# dynext_v0_1.net
KiCad netlist of a schematic drawn in EAGLE
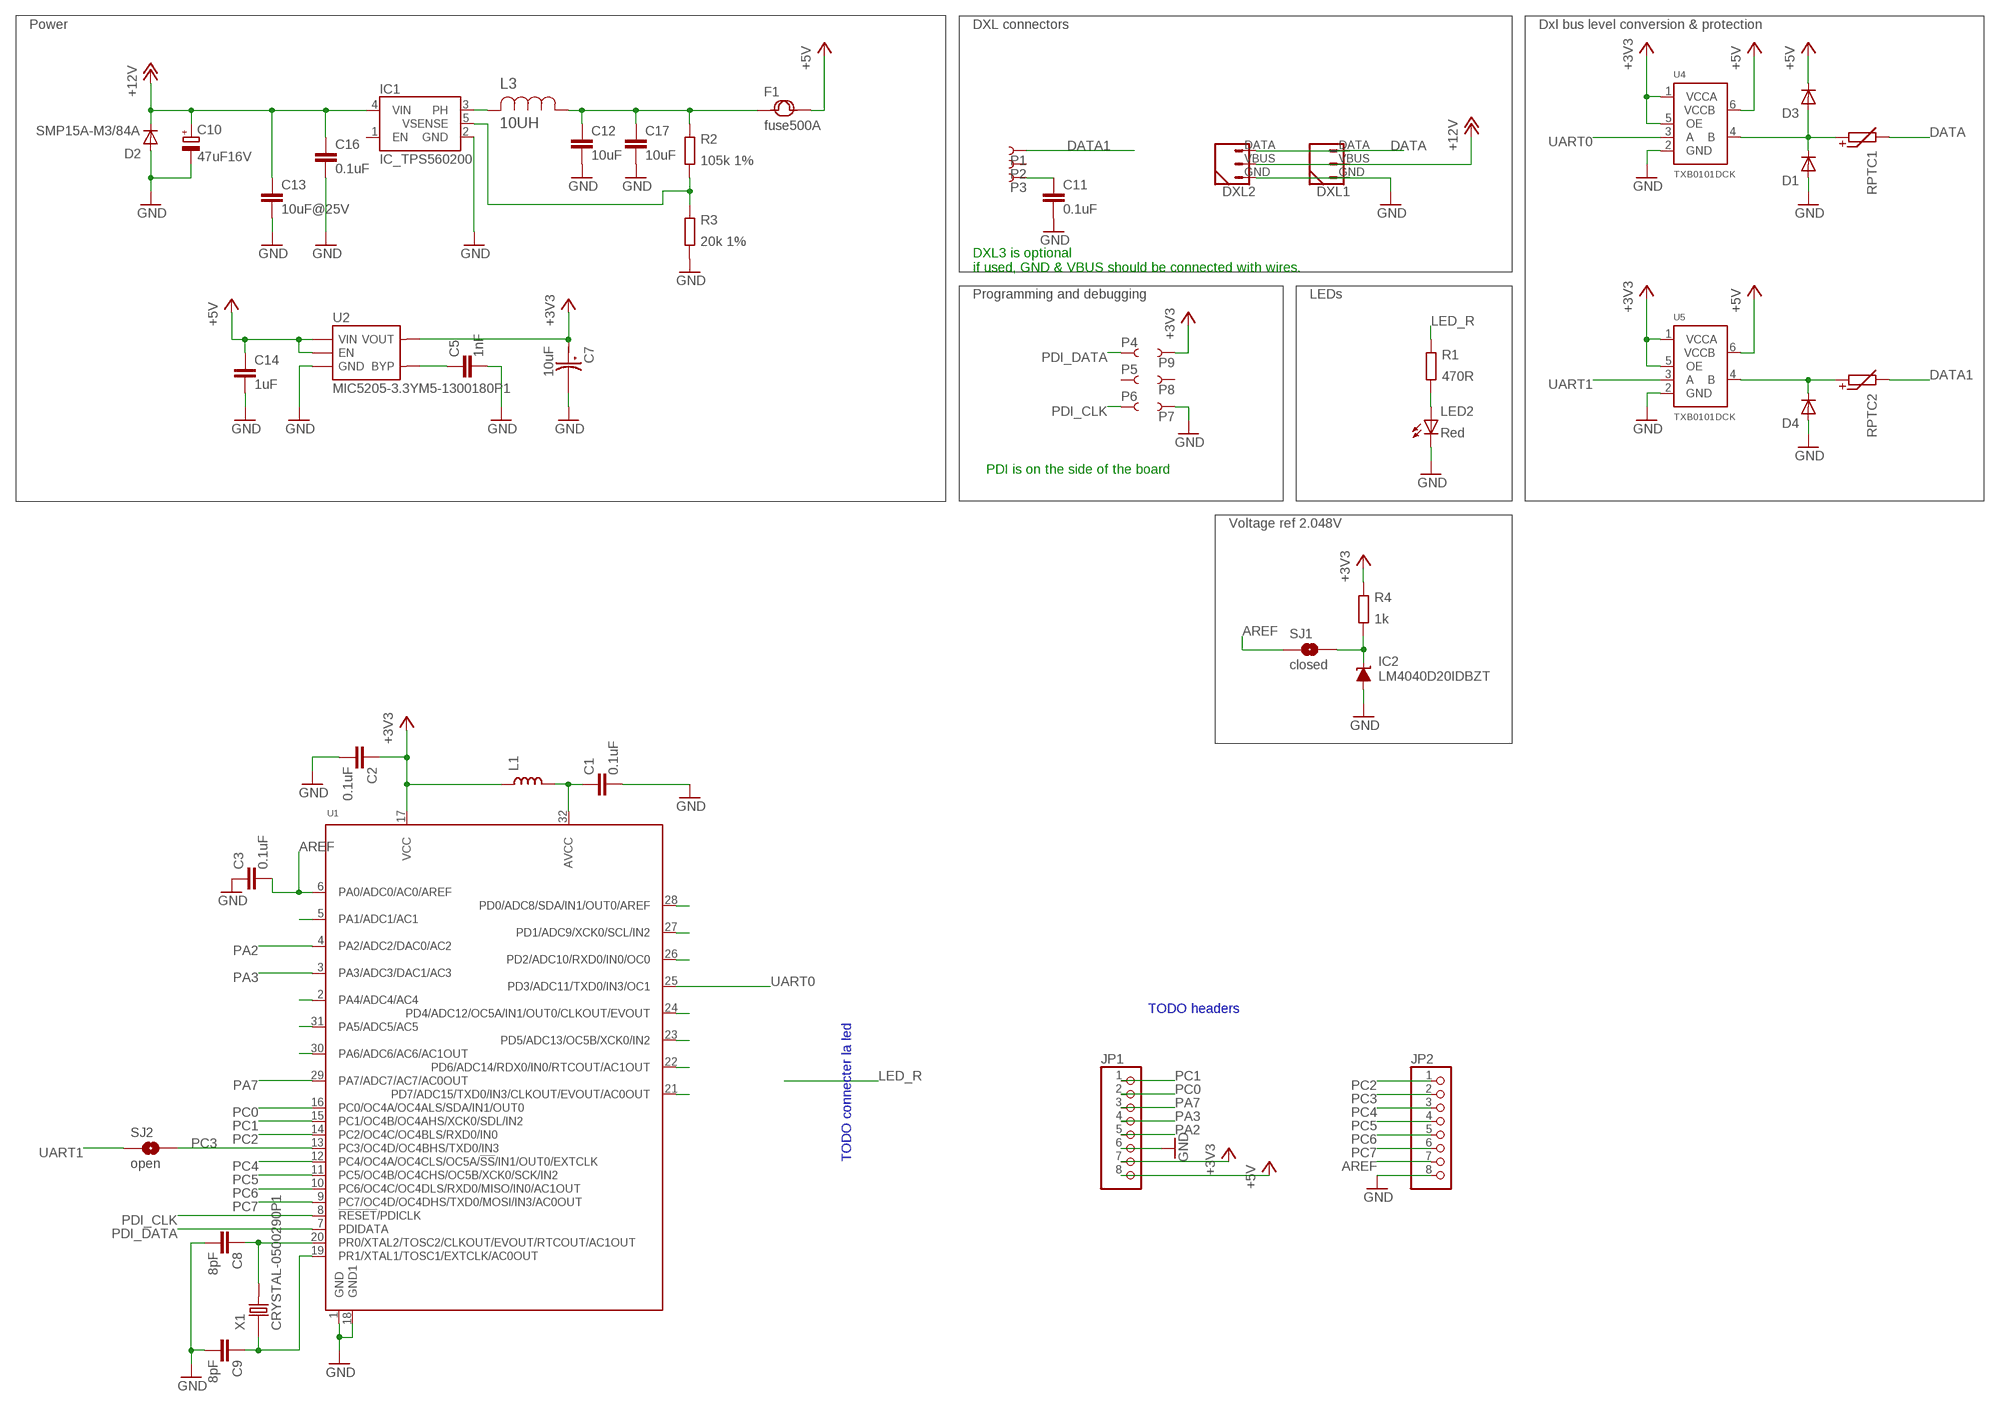
[diagram p0: schematic, sheet 1]

(export (version "E")
  (design (tool "Eeschema 10.0.6"))
  (components
    (comp (ref "C1")
      (value "0.1uF")
      (footprint "eagle-import:0402_N")
      (libsource (lib "eagle-import") (part "C0402"))
    )
    (comp (ref "C2")
      (value "0.1uF")
      (footprint "eagle-import:0402_N")
      (libsource (lib "eagle-import") (part "C0402"))
    )
    (comp (ref "C3")
      (value "0.1uF")
      (footprint "eagle-import:0402_N")
      (libsource (lib "eagle-import") (part "C0402"))
    )
    (comp (ref "C5")
      (value "1nF")
      (footprint "eagle-import:0402_N")
      (libsource (lib "eagle-import") (part "C0402"))
    )
    (comp (ref "C7")
      (value "10uF")
      (footprint "eagle-import:AVX-A")
      (libsource (lib "eagle-import") (part "C-POLAR-A"))
    )
    (comp (ref "C8")
      (value "8pF")
      (footprint "eagle-import:0402_N")
      (libsource (lib "eagle-import") (part "C0402"))
    )
    (comp (ref "C9")
      (value "8pF")
      (footprint "eagle-import:0402_N")
      (libsource (lib "eagle-import") (part "C0402"))
    )
    (comp (ref "C10")
      (value "47uF16V")
      (footprint "eagle-import:UD-5X5,8_NICHICON")
      (libsource (lib "eagle-import") (part "CPOL-EUUD-5X5,8"))
    )
    (comp (ref "C11")
      (value "0.1uF")
      (footprint "eagle-import:0402_N")
      (libsource (lib "eagle-import") (part "C0402"))
    )
    (comp (ref "C12")
      (value "10uF")
      (footprint "eagle-import:0805_N")
      (libsource (lib "eagle-import") (part "C0805"))
    )
    (comp (ref "C13")
      (value "10uF@25V")
      (footprint "eagle-import:0805_N")
      (libsource (lib "eagle-import") (part "C0805"))
    )
    (comp (ref "C14")
      (value "1uF")
      (footprint "eagle-import:0402_N")
      (libsource (lib "eagle-import") (part "C0402"))
    )
    (comp (ref "C16")
      (value "0.1uF")
      (footprint "eagle-import:0402_N")
      (libsource (lib "eagle-import") (part "C0402"))
    )
    (comp (ref "C17")
      (value "10uF")
      (footprint "eagle-import:0805_N")
      (libsource (lib "eagle-import") (part "C0805"))
    )
    (comp (ref "D1")
      (value "DIODE-SOD523")
      (footprint "eagle-import:SOD-523_N")
      (libsource (lib "eagle-import") (part "DIODE-SOD523"))
    )
    (comp (ref "D2")
      (value "SMP15A-M3/84A")
      (footprint "eagle-import:DO-220AA")
      (libsource (lib "eagle-import") (part "DIODE-SMP"))
    )
    (comp (ref "D3")
      (value "DIODE-SOD523")
      (footprint "eagle-import:SOD-523_N")
      (libsource (lib "eagle-import") (part "DIODE-SOD523"))
    )
    (comp (ref "D4")
      (value "DIODE-SOD523")
      (footprint "eagle-import:SOD-523_N")
      (libsource (lib "eagle-import") (part "DIODE-SOD523"))
    )
    (comp (ref "DXL1")
      (value "DYNAMIXEL_3POS-T")
      (footprint "eagle-import:DYNAMIXEL_3POS_TOP")
      (libsource (lib "eagle-import") (part "DYNAMIXEL_3POS-T"))
    )
    (comp (ref "DXL2")
      (value "DYNAMIXEL_3POS-T")
      (footprint "eagle-import:DYNAMIXEL_3POS_TOP")
      (libsource (lib "eagle-import") (part "DYNAMIXEL_3POS-T"))
    )
    (comp (ref "F1")
      (value "fuse500A")
      (footprint "eagle-import:F1206")
      (libsource (lib "eagle-import") (part "FUSE-1206"))
    )
    (comp (ref "IC1")
      (value "IC_TPS560200")
      (footprint "eagle-import:SOT-23-5_N")
      (libsource (lib "eagle-import") (part "IC_TPS560200"))
    )
    (comp (ref "IC2")
      (value "LM4040D20IDBZT")
      (footprint "eagle-import:DBZ_R-PDSO-G3")
      (fields (field (name "MPN") "LM4041A12IDBZR"))
      (libsource (lib "eagle-import") (part "LM4041DBZA12"))
    )
    (comp (ref "JP1")
      (value "PINHD-1X8R")
      (footprint "eagle-import:1X08_ROUND")
      (libsource (lib "eagle-import") (part "PINHD-1X8R"))
    )
    (comp (ref "JP2")
      (value "PINHD-1X8R")
      (footprint "eagle-import:1X08_ROUND")
      (libsource (lib "eagle-import") (part "PINHD-1X8R"))
    )
    (comp (ref "L1")
      (value "L0603")
      (footprint "eagle-import:0603_N")
      (libsource (lib "eagle-import") (part "L0603"))
    )
    (comp (ref "L3")
      (value "10UH")
      (footprint "eagle-import:IND_ELL4XG")
      (fields (field (name "MPN") "ELL4LG100MA"))
      (libsource (lib "eagle-import") (part "ELL-4XG4LG100MA"))
    )
    (comp (ref "LED2")
      (value "Red")
      (footprint "eagle-import:D_0603_N")
      (libsource (lib "eagle-import") (part "LED0603"))
    )
    (comp (ref "P1")
      (value "PIN_SMD_2X2.5")
      (footprint "eagle-import:PIN_SMD_2X2.5")
      (libsource (lib "eagle-import") (part "PIN_SMD_2X2.5"))
    )
    (comp (ref "P2")
      (value "PIN_SMD_2X2.5")
      (footprint "eagle-import:PIN_SMD_2X2.5")
      (libsource (lib "eagle-import") (part "PIN_SMD_2X2.5"))
    )
    (comp (ref "P3")
      (value "PIN_SMD_2X2.5")
      (footprint "eagle-import:PIN_SMD_2X2.5")
      (libsource (lib "eagle-import") (part "PIN_SMD_2X2.5"))
    )
    (comp (ref "P4")
      (value "PIN_SMD_2X2.5")
      (footprint "eagle-import:PIN_SMD_2X2.5")
      (libsource (lib "eagle-import") (part "PIN_SMD_2X2.5"))
    )
    (comp (ref "P5")
      (value "PIN_SMD_1X1")
      (footprint "eagle-import:PIN_SMD_1X1")
      (libsource (lib "eagle-import") (part "PIN_SMD_1X1"))
    )
    (comp (ref "P6")
      (value "PIN_SMD_2X2.5")
      (footprint "eagle-import:PIN_SMD_2X2.5")
      (libsource (lib "eagle-import") (part "PIN_SMD_2X2.5"))
    )
    (comp (ref "P7")
      (value "PIN_SMD_2X2.5")
      (footprint "eagle-import:PIN_SMD_2X2.5")
      (libsource (lib "eagle-import") (part "PIN_SMD_2X2.5"))
    )
    (comp (ref "P8")
      (value "PIN_SMD_1X1")
      (footprint "eagle-import:PIN_SMD_1X1")
      (libsource (lib "eagle-import") (part "PIN_SMD_1X1"))
    )
    (comp (ref "P9")
      (value "PIN_SMD_2X2.5")
      (footprint "eagle-import:PIN_SMD_2X2.5")
      (libsource (lib "eagle-import") (part "PIN_SMD_2X2.5"))
    )
    (comp (ref "R1")
      (value "470R")
      (footprint "eagle-import:0402_N")
      (libsource (lib "eagle-import") (part "R0402"))
    )
    (comp (ref "R2")
      (value "105k 1%")
      (footprint "eagle-import:0402_N")
      (libsource (lib "eagle-import") (part "R0402"))
    )
    (comp (ref "R3")
      (value "20k 1%")
      (footprint "eagle-import:0402_N")
      (libsource (lib "eagle-import") (part "R0402"))
    )
    (comp (ref "R4")
      (value "1k")
      (footprint "eagle-import:0402_N")
      (libsource (lib "eagle-import") (part "R0402"))
    )
    (comp (ref "RPTC1")
      (value "R-PTC0603")
      (footprint "eagle-import:0603_N")
      (libsource (lib "eagle-import") (part "R-PTC0603"))
    )
    (comp (ref "RPTC2")
      (value "R-PTC0603")
      (footprint "eagle-import:0603_N")
      (libsource (lib "eagle-import") (part "R-PTC0603"))
    )
    (comp (ref "SJ1")
      (value "closed")
      (footprint "eagle-import:SJ_2S-TRACE2")
      (libsource (lib "eagle-import") (part "SOLDERJUMPER2_TRACE2"))
    )
    (comp (ref "SJ2")
      (value "open")
      (footprint "eagle-import:SJ_2S-NO")
      (libsource (lib "eagle-import") (part "SOLDERJUMPER2NO"))
    )
    (comp (ref "U1")
      (value "ATXMEGAE5-MU_MOD")
      (footprint "eagle-import:QFN-32_50P_L_MOD")
      (libsource (lib "eagle-import") (part "ATXMEGAE5-MU_MOD"))
    )
    (comp (ref "U2")
      (value "MIC5205-3.3YM5-1300180P1")
      (footprint "eagle-import:SOT23-5")
      (libsource (lib "eagle-import") (part "MIC5205-3.3YM5-1300180P1"))
    )
    (comp (ref "U4")
      (value "TXB0101DCK")
      (footprint "eagle-import:SC70-6")
      (libsource (lib "eagle-import") (part "TXB0101DCK"))
    )
    (comp (ref "U5")
      (value "TXB0101DCK")
      (footprint "eagle-import:SC70-6")
      (libsource (lib "eagle-import") (part "TXB0101DCK"))
    )
    (comp (ref "X1")
      (value "CRYSTAL-0500290P1")
      (footprint "eagle-import:2P-SMD-5.0X3.2")
      (libsource (lib "eagle-import") (part "CRYSTAL-0500290P1"))
    )
  )
  (nets
    (net (code "1") (name "+3V3") (class "Default")
      (node (ref "C2") (pin "1") (pinfunction "1_1") (pintype "passive"))
      (node (ref "C7") (pin "+") (pinfunction "1_+") (pintype "bidirectional"))
      (node (ref "JP1") (pin "7") (pinfunction "7_7") (pintype "passive"))
      (node (ref "L1") (pin "1") (pinfunction "1_1") (pintype "passive"))
      (node (ref "P9") (pin "PIN") (pinfunction "1_PIN") (pintype "bidirectional"))
      (node (ref "R4") (pin "2") (pinfunction "2_2") (pintype "passive"))
      (node (ref "U1") (pin "17") (pinfunction "VCC_17") (pintype "bidirectional"))
      (node (ref "U2") (pin "5") (pinfunction "VOUT_5") (pintype "bidirectional"))
      (node (ref "U4") (pin "1") (pinfunction "VCCA_1") (pintype "bidirectional"))
      (node (ref "U4") (pin "5") (pinfunction "OE_5") (pintype "bidirectional"))
      (node (ref "U5") (pin "1") (pinfunction "VCCA_1") (pintype "bidirectional"))
      (node (ref "U5") (pin "5") (pinfunction "OE_5") (pintype "bidirectional"))
    )
    (net (code "2") (name "+5V") (class "Default")
      (node (ref "C14") (pin "1") (pinfunction "1_1") (pintype "passive"))
      (node (ref "D3") (pin "C") (pinfunction "C_C") (pintype "passive"))
      (node (ref "F1") (pin "2") (pinfunction "2_2") (pintype "bidirectional"))
      (node (ref "JP1") (pin "8") (pinfunction "8_8") (pintype "passive"))
      (node (ref "U2") (pin "1") (pinfunction "VIN_1") (pintype "bidirectional"))
      (node (ref "U2") (pin "3") (pinfunction "EN_3") (pintype "bidirectional"))
      (node (ref "U4") (pin "6") (pinfunction "VCCB_6") (pintype "bidirectional"))
      (node (ref "U5") (pin "6") (pinfunction "VCCB_6") (pintype "bidirectional"))
    )
    (net (code "3") (name "+12V") (class "Default")
      (node (ref "C10") (pin "+") (pinfunction "+_+") (pintype "passive"))
      (node (ref "C13") (pin "1") (pinfunction "1_1") (pintype "passive"))
      (node (ref "C16") (pin "1") (pinfunction "1_1") (pintype "passive"))
      (node (ref "D2") (pin "C") (pinfunction "C_C") (pintype "passive"))
      (node (ref "DXL1") (pin "VBUS") (pinfunction "2_VBUS") (pintype "bidirectional"))
      (node (ref "DXL2") (pin "VBUS") (pinfunction "2_VBUS") (pintype "bidirectional"))
      (node (ref "IC1") (pin "4") (pinfunction "VIN_4") (pintype "bidirectional"))
    )
    (net (code "4") (name "/AREF") (class "Default")
      (node (ref "C3") (pin "2") (pinfunction "2_2") (pintype "passive"))
      (node (ref "JP2") (pin "7") (pinfunction "7_7") (pintype "passive"))
      (node (ref "SJ1") (pin "1") (pinfunction "1_1") (pintype "passive"))
      (node (ref "U1") (pin "6") (pinfunction "PA0/ADC0/AC0/AREF_6") (pintype "bidirectional"))
    )
    (net (code "5") (name "/DATA") (class "Default")
      (node (ref "DXL1") (pin "DATA") (pinfunction "3_DATA") (pintype "bidirectional"))
      (node (ref "DXL2") (pin "DATA") (pinfunction "3_DATA") (pintype "bidirectional"))
      (node (ref "RPTC1") (pin "2") (pinfunction "2_2") (pintype "passive"))
    )
    (net (code "6") (name "/DATA1") (class "Default")
      (node (ref "P1") (pin "PIN") (pinfunction "1_PIN") (pintype "bidirectional"))
      (node (ref "RPTC2") (pin "2") (pinfunction "2_2") (pintype "passive"))
    )
    (net (code "7") (name "/LED_R") (class "Default")
      (node (ref "R1") (pin "2") (pinfunction "2_2") (pintype "passive"))
    )
    (net (code "8") (name "/PA2") (class "Default")
      (node (ref "JP1") (pin "5") (pinfunction "5_5") (pintype "passive"))
      (node (ref "U1") (pin "4") (pinfunction "PA2/ADC2/DAC0/AC2_4") (pintype "bidirectional"))
    )
    (net (code "9") (name "/PA3") (class "Default")
      (node (ref "JP1") (pin "4") (pinfunction "4_4") (pintype "passive"))
      (node (ref "U1") (pin "3") (pinfunction "PA3/ADC3/DAC1/AC3_3") (pintype "bidirectional"))
    )
    (net (code "10") (name "/PA7") (class "Default")
      (node (ref "JP1") (pin "3") (pinfunction "3_3") (pintype "passive"))
      (node (ref "U1") (pin "29") (pinfunction "PA7/ADC7/AC7/AC0OUT_29") (pintype "bidirectional"))
    )
    (net (code "11") (name "/PC0") (class "Default")
      (node (ref "JP1") (pin "2") (pinfunction "2_2") (pintype "passive"))
      (node (ref "U1") (pin "16") (pinfunction "PC0/OC4A/OC4ALS/SDA/IN1/OUT0_16") (pintype "bidirectional"))
    )
    (net (code "12") (name "/PC1") (class "Default")
      (node (ref "JP1") (pin "1") (pinfunction "1_1") (pintype "passive"))
      (node (ref "U1") (pin "15") (pinfunction "PC1/OC4B/OC4AHS/XCK0/SDL/IN2_15") (pintype "bidirectional"))
    )
    (net (code "13") (name "/PC2") (class "Default")
      (node (ref "JP2") (pin "1") (pinfunction "1_1") (pintype "passive"))
      (node (ref "U1") (pin "14") (pinfunction "PC2/OC4C/OC4BLS/RXD0/IN0_14") (pintype "bidirectional"))
    )
    (net (code "14") (name "/PC3") (class "Default")
      (node (ref "JP2") (pin "2") (pinfunction "2_2") (pintype "passive"))
      (node (ref "SJ2") (pin "2") (pinfunction "2_2") (pintype "passive"))
      (node (ref "U1") (pin "13") (pinfunction "PC3/OC4D/OC4BHS/TXD0/IN3_13") (pintype "bidirectional"))
    )
    (net (code "15") (name "/PC4") (class "Default")
      (node (ref "JP2") (pin "3") (pinfunction "3_3") (pintype "passive"))
      (node (ref "U1") (pin "12") (pinfunction "PC4/OC4A/OC4CLS/OC5A/~{SS}/IN1/OUT0/EXTCLK_12") (pintype "bidirectional"))
    )
    (net (code "16") (name "/PC5") (class "Default")
      (node (ref "JP2") (pin "4") (pinfunction "4_4") (pintype "passive"))
      (node (ref "U1") (pin "11") (pinfunction "PC5/OC4B/OC4CHS/OC5B/XCK0/SCK/IN2_11") (pintype "bidirectional"))
    )
    (net (code "17") (name "/PC6") (class "Default")
      (node (ref "JP2") (pin "5") (pinfunction "5_5") (pintype "passive"))
      (node (ref "U1") (pin "10") (pinfunction "PC6/OC4C/OC4DLS/RXD0/MISO/IN0/AC1OUT_10") (pintype "bidirectional"))
    )
    (net (code "18") (name "/PC7") (class "Default")
      (node (ref "JP2") (pin "6") (pinfunction "6_6") (pintype "passive"))
      (node (ref "U1") (pin "9") (pinfunction "PC7/OC4D/OC4DHS/TXD0/MOSI/IN3/AC0OUT_9") (pintype "bidirectional"))
    )
    (net (code "19") (name "/PDI_CLK") (class "Default")
      (node (ref "P6") (pin "PIN") (pinfunction "1_PIN") (pintype "bidirectional"))
      (node (ref "U1") (pin "8") (pinfunction "~{RESET}/PDICLK_8") (pintype "bidirectional"))
    )
    (net (code "20") (name "/PDI_DATA") (class "Default")
      (node (ref "P4") (pin "PIN") (pinfunction "1_PIN") (pintype "bidirectional"))
      (node (ref "U1") (pin "7") (pinfunction "PDIDATA_7") (pintype "bidirectional"))
    )
    (net (code "21") (name "/UART0") (class "Default")
      (node (ref "U1") (pin "25") (pinfunction "PD3/ADC11/TXD0/IN3/OC1_25") (pintype "bidirectional"))
      (node (ref "U4") (pin "3") (pinfunction "A_3") (pintype "bidirectional"))
    )
    (net (code "22") (name "/UART1") (class "Default")
      (node (ref "SJ2") (pin "1") (pinfunction "1_1") (pintype "passive"))
      (node (ref "U5") (pin "3") (pinfunction "A_3") (pintype "bidirectional"))
    )
    (net (code "23") (name "GND") (class "Default")
      (node (ref "C1") (pin "2") (pinfunction "2_2") (pintype "passive"))
      (node (ref "C10") (pin "-") (pinfunction "-_-") (pintype "passive"))
      (node (ref "C11") (pin "2") (pinfunction "2_2") (pintype "passive"))
      (node (ref "C12") (pin "2") (pinfunction "2_2") (pintype "passive"))
      (node (ref "C13") (pin "2") (pinfunction "2_2") (pintype "passive"))
      (node (ref "C14") (pin "2") (pinfunction "2_2") (pintype "passive"))
      (node (ref "C16") (pin "2") (pinfunction "2_2") (pintype "passive"))
      (node (ref "C17") (pin "2") (pinfunction "2_2") (pintype "passive"))
      (node (ref "C2") (pin "2") (pinfunction "2_2") (pintype "passive"))
      (node (ref "C3") (pin "1") (pinfunction "1_1") (pintype "passive"))
      (node (ref "C5") (pin "2") (pinfunction "2_2") (pintype "passive"))
      (node (ref "C7") (pin "-") (pinfunction "2_-") (pintype "bidirectional"))
      (node (ref "C8") (pin "2") (pinfunction "2_2") (pintype "passive"))
      (node (ref "C9") (pin "2") (pinfunction "2_2") (pintype "passive"))
      (node (ref "D1") (pin "A") (pinfunction "A_A") (pintype "passive"))
      (node (ref "D2") (pin "A") (pinfunction "A_A") (pintype "passive"))
      (node (ref "D4") (pin "A") (pinfunction "A_A") (pintype "passive"))
      (node (ref "DXL1") (pin "GND") (pinfunction "1_GND") (pintype "bidirectional"))
      (node (ref "DXL2") (pin "GND") (pinfunction "1_GND") (pintype "bidirectional"))
      (node (ref "IC1") (pin "2") (pinfunction "GND_2") (pintype "input"))
      (node (ref "IC2") (pin "2") (pinfunction "A_2") (pintype "passive"))
      (node (ref "JP1") (pin "6") (pinfunction "6_6") (pintype "passive"))
      (node (ref "JP2") (pin "8") (pinfunction "8_8") (pintype "passive"))
      (node (ref "LED2") (pin "C") (pinfunction "C_C") (pintype "passive"))
      (node (ref "P7") (pin "PIN") (pinfunction "1_PIN") (pintype "bidirectional"))
      (node (ref "R3") (pin "1") (pinfunction "1_1") (pintype "passive"))
      (node (ref "U1") (pin "1") (pinfunction "GND_1") (pintype "bidirectional"))
      (node (ref "U1") (pin "18") (pinfunction "GND1_18") (pintype "bidirectional"))
      (node (ref "U2") (pin "2") (pinfunction "GND_2") (pintype "bidirectional"))
      (node (ref "U4") (pin "2") (pinfunction "GND_2") (pintype "bidirectional"))
      (node (ref "U5") (pin "2") (pinfunction "GND_2") (pintype "bidirectional"))
    )
    (net (code "24") (name "Net-(C12-Pad1)") (class "Default")
      (node (ref "C12") (pin "1") (pinfunction "1_1") (pintype "passive"))
      (node (ref "C17") (pin "1") (pinfunction "1_1") (pintype "passive"))
      (node (ref "F1") (pin "1") (pinfunction "1_1") (pintype "bidirectional"))
      (node (ref "L3") (pin "1") (pinfunction "1_1") (pintype "passive"))
      (node (ref "R2") (pin "2") (pinfunction "2_2") (pintype "passive"))
    )
    (net (code "25") (name "Net-(IC1-PH)") (class "Default")
      (node (ref "IC1") (pin "3") (pinfunction "PH_3") (pintype "bidirectional"))
      (node (ref "L3") (pin "2") (pinfunction "2_2") (pintype "passive"))
    )
    (net (code "26") (name "Net-(IC1-VSENSE)") (class "Default")
      (node (ref "IC1") (pin "5") (pinfunction "VSENSE_5") (pintype "bidirectional"))
      (node (ref "R2") (pin "1") (pinfunction "1_1") (pintype "passive"))
      (node (ref "R3") (pin "2") (pinfunction "2_2") (pintype "passive"))
    )
    (net (code "27") (name "Net-(IC2-C)") (class "Default")
      (node (ref "IC2") (pin "1") (pinfunction "C_1") (pintype "passive"))
      (node (ref "R4") (pin "1") (pinfunction "1_1") (pintype "passive"))
      (node (ref "SJ1") (pin "2") (pinfunction "2_2") (pintype "passive"))
    )
    (net (code "28") (name "Net-(LED2-PadA)") (class "Default")
      (node (ref "LED2") (pin "A") (pinfunction "A_A") (pintype "passive"))
      (node (ref "R1") (pin "1") (pinfunction "1_1") (pintype "passive"))
    )
    (net (code "29") (name "Net-(P3-1)") (class "Default")
      (node (ref "C11") (pin "1") (pinfunction "1_1") (pintype "passive"))
      (node (ref "P3") (pin "PIN") (pinfunction "1_PIN") (pintype "bidirectional"))
    )
    (net (code "30") (name "Net-(U1-AVCC)") (class "Default")
      (node (ref "C1") (pin "1") (pinfunction "1_1") (pintype "passive"))
      (node (ref "L1") (pin "2") (pinfunction "2_2") (pintype "passive"))
      (node (ref "U1") (pin "32") (pinfunction "AVCC_32") (pintype "bidirectional"))
    )
    (net (code "31") (name "Net-(U1-PR0{slash}XTAL2{slash}TOSC2{slash}CLKOUT{slash}EVOUT{slash}RTCOUT{slash}AC1OUT)") (class "Default")
      (node (ref "C8") (pin "1") (pinfunction "1_1") (pintype "passive"))
      (node (ref "U1") (pin "20") (pinfunction "PR0/XTAL2/TOSC2/CLKOUT/EVOUT/RTCOUT/AC1OUT_20") (pintype "bidirectional"))
      (node (ref "X1") (pin "2") (pinfunction "2_2") (pintype "passive"))
    )
    (net (code "32") (name "Net-(U1-PR1{slash}XTAL1{slash}TOSC1{slash}EXTCLK{slash}AC0OUT)") (class "Default")
      (node (ref "C9") (pin "1") (pinfunction "1_1") (pintype "passive"))
      (node (ref "U1") (pin "19") (pinfunction "PR1/XTAL1/TOSC1/EXTCLK/AC0OUT_19") (pintype "bidirectional"))
      (node (ref "X1") (pin "1") (pinfunction "1_1") (pintype "passive"))
    )
    (net (code "33") (name "Net-(U2-BYP)") (class "Default")
      (node (ref "C5") (pin "1") (pinfunction "1_1") (pintype "passive"))
      (node (ref "U2") (pin "4") (pinfunction "BYP_4") (pintype "bidirectional"))
    )
    (net (code "34") (name "Net-(U4-B)") (class "Default")
      (node (ref "D1") (pin "C") (pinfunction "C_C") (pintype "passive"))
      (node (ref "D3") (pin "A") (pinfunction "A_A") (pintype "passive"))
      (node (ref "RPTC1") (pin "1") (pinfunction "1_1") (pintype "passive"))
      (node (ref "U4") (pin "4") (pinfunction "B_4") (pintype "bidirectional"))
    )
    (net (code "35") (name "Net-(U5-B)") (class "Default")
      (node (ref "D4") (pin "C") (pinfunction "C_C") (pintype "passive"))
      (node (ref "RPTC2") (pin "1") (pinfunction "1_1") (pintype "passive"))
      (node (ref "U5") (pin "4") (pinfunction "B_4") (pintype "bidirectional"))
    )
    (net (code "36") (name "unconnected-(IC1-EN-Pad1)") (class "Default")
      (node (ref "IC1") (pin "1") (pinfunction "EN_1") (pintype "input"))
    )
    (net (code "37") (name "unconnected-(P2-1-PadPIN)") (class "Default")
      (node (ref "P2") (pin "PIN") (pinfunction "1_PIN") (pintype "bidirectional"))
    )
    (net (code "38") (name "unconnected-(P5-1-PadP$1)") (class "Default")
      (node (ref "P5") (pin "P$1") (pinfunction "1_P$1") (pintype "bidirectional"))
    )
    (net (code "39") (name "unconnected-(P8-1-PadP$1)") (class "Default")
      (node (ref "P8") (pin "P$1") (pinfunction "1_P$1") (pintype "bidirectional"))
    )
    (net (code "40") (name "unconnected-(U1-PA1{slash}ADC1{slash}AC1-Pad5)") (class "Default")
      (node (ref "U1") (pin "5") (pinfunction "PA1/ADC1/AC1_5") (pintype "bidirectional"))
    )
    (net (code "41") (name "unconnected-(U1-PA4{slash}ADC4{slash}AC4-Pad2)") (class "Default")
      (node (ref "U1") (pin "2") (pinfunction "PA4/ADC4/AC4_2") (pintype "bidirectional"))
    )
    (net (code "42") (name "unconnected-(U1-PA5{slash}ADC5{slash}AC5-Pad31)") (class "Default")
      (node (ref "U1") (pin "31") (pinfunction "PA5/ADC5/AC5_31") (pintype "bidirectional"))
    )
    (net (code "43") (name "unconnected-(U1-PA6{slash}ADC6{slash}AC6{slash}AC1OUT-Pad30)") (class "Default")
      (node (ref "U1") (pin "30") (pinfunction "PA6/ADC6/AC6/AC1OUT_30") (pintype "bidirectional"))
    )
    (net (code "44") (name "unconnected-(U1-PD0{slash}ADC8{slash}SDA{slash}IN1{slash}OUT0{slash}AREF-Pad28)") (class "Default")
      (node (ref "U1") (pin "28") (pinfunction "PD0/ADC8/SDA/IN1/OUT0/AREF_28") (pintype "bidirectional"))
    )
    (net (code "45") (name "unconnected-(U1-PD1{slash}ADC9{slash}XCK0{slash}SCL{slash}IN2-Pad27)") (class "Default")
      (node (ref "U1") (pin "27") (pinfunction "PD1/ADC9/XCK0/SCL/IN2_27") (pintype "bidirectional"))
    )
    (net (code "46") (name "unconnected-(U1-PD2{slash}ADC10{slash}RXD0{slash}IN0{slash}OC0-Pad26)") (class "Default")
      (node (ref "U1") (pin "26") (pinfunction "PD2/ADC10/RXD0/IN0/OC0_26") (pintype "bidirectional"))
    )
    (net (code "47") (name "unconnected-(U1-PD4{slash}ADC12{slash}OC5A{slash}IN1{slash}OUT0{slash}CLKOUT{slash}EVOUT-Pad24)") (class "Default")
      (node (ref "U1") (pin "24") (pinfunction "PD4/ADC12/OC5A/IN1/OUT0/CLKOUT/EVOUT_24") (pintype "bidirectional"))
    )
    (net (code "48") (name "unconnected-(U1-PD5{slash}ADC13{slash}OC5B{slash}XCK0{slash}IN2-Pad23)") (class "Default")
      (node (ref "U1") (pin "23") (pinfunction "PD5/ADC13/OC5B/XCK0/IN2_23") (pintype "bidirectional"))
    )
    (net (code "49") (name "unconnected-(U1-PD6{slash}ADC14{slash}RDX0{slash}IN0{slash}RTCOUT{slash}AC1OUT-Pad22)") (class "Default")
      (node (ref "U1") (pin "22") (pinfunction "PD6/ADC14/RDX0/IN0/RTCOUT/AC1OUT_22") (pintype "bidirectional"))
    )
    (net (code "50") (name "unconnected-(U1-PD7{slash}ADC15{slash}TXD0{slash}IN3{slash}CLKOUT{slash}EVOUT{slash}AC0OUT-Pad21)") (class "Default")
      (node (ref "U1") (pin "21") (pinfunction "PD7/ADC15/TXD0/IN3/CLKOUT/EVOUT/AC0OUT_21") (pintype "bidirectional"))
    )
  )
)
